# 06_-_FPGA_Aux.net
KiCad netlist of a schematic drawn in Altium Designer
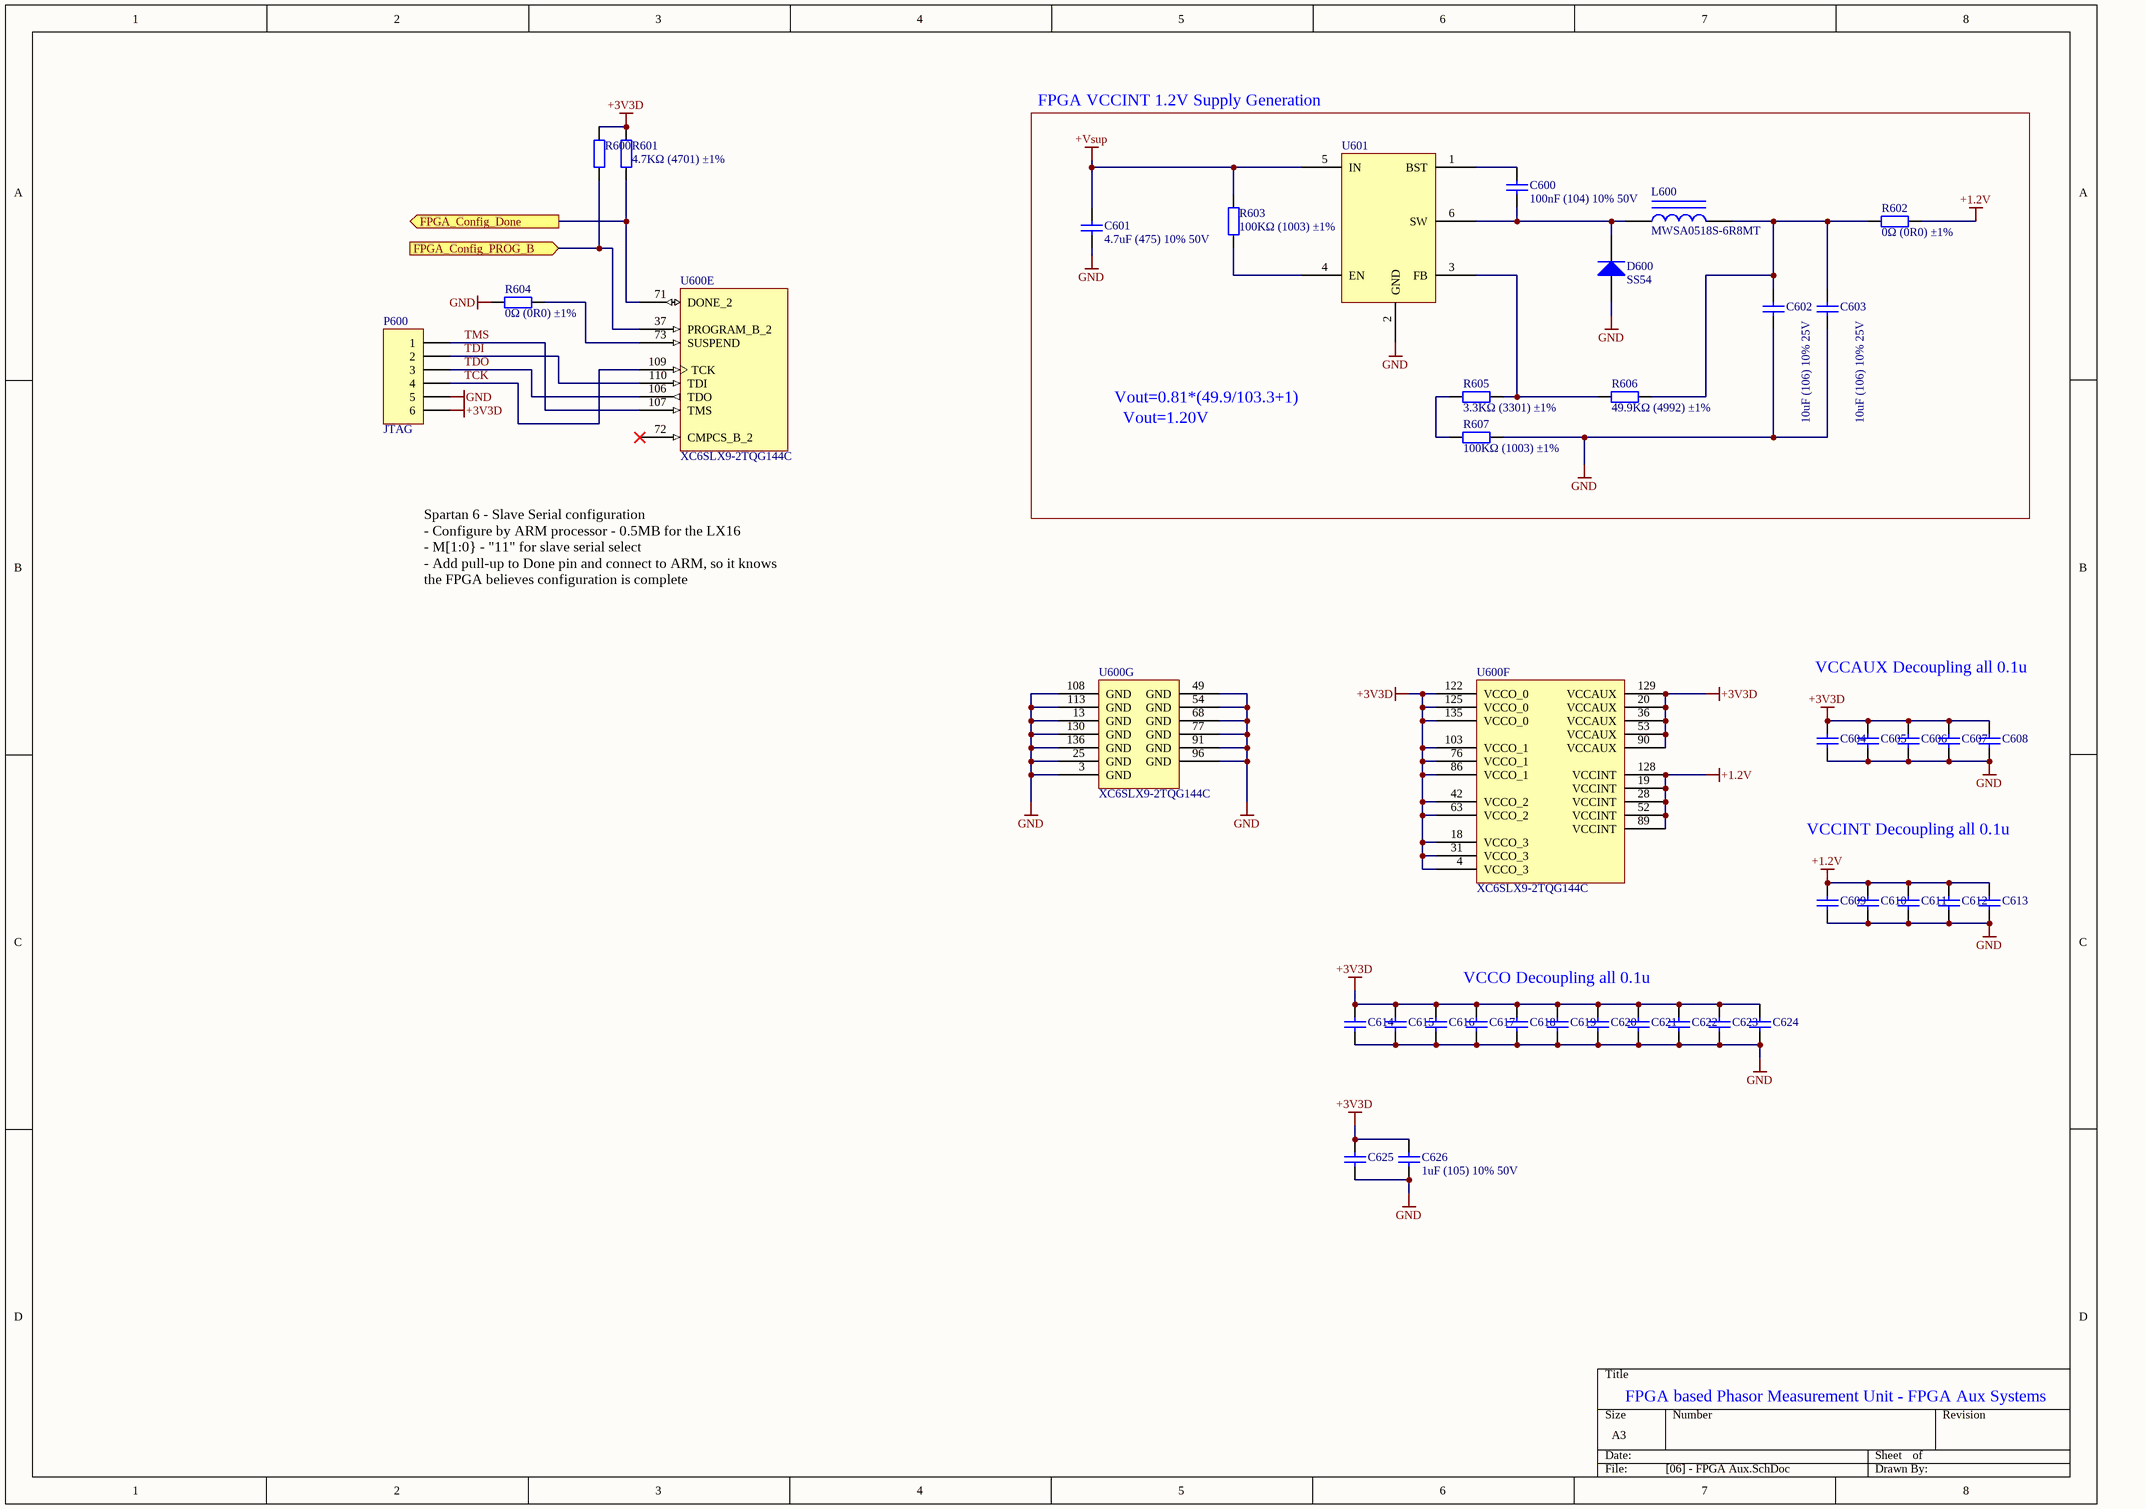
[diagram p0: [06] - FPGA Aux.SchDoc]

(export (version "E")
  (design (tool "Eeschema 10.0.6"))
  (components
    (comp (ref "C600")
      (value "100nF (104) 10% 50V")
      (footprint "0603_C")
      (description "贴片电容")
      (libsource (lib "Cap") (part "0603 100nF (104) 10% 50V"))
    )
    (comp (ref "C601")
      (value "4.7uF (475) 10% 50V")
      (footprint "1206_C")
      (description "贴片电容")
      (libsource (lib "Cap") (part "1206 4.7uF (475) 10% 50V"))
    )
    (comp (ref "C602")
      (value "10uF (106) 10% 25V")
      (footprint "0805_C")
      (description "贴片电容")
      (libsource (lib "Cap") (part "0805 10uF (106) 10% 25V"))
    )
    (comp (ref "C603")
      (value "10uF (106) 10% 25V")
      (footprint "0805_C")
      (description "贴片电容")
      (libsource (lib "Cap") (part "0805 10uF (106) 10% 25V"))
    )
    (comp (ref "C604")
      (value "100nF (104) 10% 16V")
      (footprint "0402_C")
      (description "贴片电容")
      (libsource (lib "Cap") (part "0402 100nF (104) 10% 16V"))
    )
    (comp (ref "C605")
      (value "100nF (104) 10% 16V")
      (footprint "0402_C")
      (description "贴片电容")
      (libsource (lib "Cap") (part "0402 100nF (104) 10% 16V"))
    )
    (comp (ref "C606")
      (value "100nF (104) 10% 16V")
      (footprint "0402_C")
      (description "贴片电容")
      (libsource (lib "Cap") (part "0402 100nF (104) 10% 16V"))
    )
    (comp (ref "C607")
      (value "100nF (104) 10% 16V")
      (footprint "0402_C")
      (description "贴片电容")
      (libsource (lib "Cap") (part "0402 100nF (104) 10% 16V"))
    )
    (comp (ref "C608")
      (value "100nF (104) 10% 16V")
      (footprint "0402_C")
      (description "贴片电容")
      (libsource (lib "Cap") (part "0402 100nF (104) 10% 16V"))
    )
    (comp (ref "C609")
      (value "100nF (104) 10% 16V")
      (footprint "0402_C")
      (description "贴片电容")
      (libsource (lib "Cap") (part "0402 100nF (104) 10% 16V"))
    )
    (comp (ref "C610")
      (value "100nF (104) 10% 16V")
      (footprint "0402_C")
      (description "贴片电容")
      (libsource (lib "Cap") (part "0402 100nF (104) 10% 16V"))
    )
    (comp (ref "C611")
      (value "100nF (104) 10% 16V")
      (footprint "0402_C")
      (description "贴片电容")
      (libsource (lib "Cap") (part "0402 100nF (104) 10% 16V"))
    )
    (comp (ref "C612")
      (value "100nF (104) 10% 16V")
      (footprint "0402_C")
      (description "贴片电容")
      (libsource (lib "Cap") (part "0402 100nF (104) 10% 16V"))
    )
    (comp (ref "C613")
      (value "100nF (104) 10% 16V")
      (footprint "0402_C")
      (description "贴片电容")
      (libsource (lib "Cap") (part "0402 100nF (104) 10% 16V"))
    )
    (comp (ref "C614")
      (value "100nF (104) 10% 16V")
      (footprint "0402_C")
      (description "贴片电容")
      (libsource (lib "Cap") (part "0402 100nF (104) 10% 16V"))
    )
    (comp (ref "C615")
      (value "100nF (104) 10% 16V")
      (footprint "0402_C")
      (description "贴片电容")
      (libsource (lib "Cap") (part "0402 100nF (104) 10% 16V"))
    )
    (comp (ref "C616")
      (value "100nF (104) 10% 16V")
      (footprint "0402_C")
      (description "贴片电容")
      (libsource (lib "Cap") (part "0402 100nF (104) 10% 16V"))
    )
    (comp (ref "C617")
      (value "100nF (104) 10% 16V")
      (footprint "0402_C")
      (description "贴片电容")
      (libsource (lib "Cap") (part "0402 100nF (104) 10% 16V"))
    )
    (comp (ref "C618")
      (value "100nF (104) 10% 16V")
      (footprint "0402_C")
      (description "贴片电容")
      (libsource (lib "Cap") (part "0402 100nF (104) 10% 16V"))
    )
    (comp (ref "C619")
      (value "100nF (104) 10% 16V")
      (footprint "0402_C")
      (description "贴片电容")
      (libsource (lib "Cap") (part "0402 100nF (104) 10% 16V"))
    )
    (comp (ref "C620")
      (value "100nF (104) 10% 16V")
      (footprint "0402_C")
      (description "贴片电容")
      (libsource (lib "Cap") (part "0402 100nF (104) 10% 16V"))
    )
    (comp (ref "C621")
      (value "100nF (104) 10% 16V")
      (footprint "0402_C")
      (description "贴片电容")
      (libsource (lib "Cap") (part "0402 100nF (104) 10% 16V"))
    )
    (comp (ref "C622")
      (value "100nF (104) 10% 16V")
      (footprint "0402_C")
      (description "贴片电容")
      (libsource (lib "Cap") (part "0402 100nF (104) 10% 16V"))
    )
    (comp (ref "C623")
      (value "100nF (104) 10% 16V")
      (footprint "0402_C")
      (description "贴片电容")
      (libsource (lib "Cap") (part "0402 100nF (104) 10% 16V"))
    )
    (comp (ref "C624")
      (value "100nF (104) 10% 16V")
      (footprint "0402_C")
      (description "贴片电容")
      (libsource (lib "Cap") (part "0402 100nF (104) 10% 16V"))
    )
    (comp (ref "C625")
      (value "1uF (105) 10% 50V")
      (footprint "0603_C")
      (description "贴片电容")
      (libsource (lib "Cap") (part "0603 1uF (105) 10% 50V"))
    )
    (comp (ref "C626")
      (value "1uF (105) 10% 50V")
      (footprint "0603_C")
      (description "贴片电容")
      (libsource (lib "Cap") (part "0603 1uF (105) 10% 50V"))
    )
    (comp (ref "D600")
      (value "SS54")
      (footprint "SMA(DO-214AC)_S1")
      (description "二极管")
      (libsource (lib "Diode") (part "SMA(DO-214AC) SS54"))
    )
    (comp (ref "L600")
      (value "MWSA0518S-6R8MT")
      (footprint "MWSA0518")
      (description "POWER INDUCTORS SMD,5.2X5.4X1.8MM ROHS")
      (libsource (lib "FPGA_PMU_lib") (part "MWSA0518S-6R8MT"))
    )
    (comp (ref "P600")
      (value "JTAG")
      (footprint "HDR1X6")
      (description "Header, 6-Pin")
      (fields (field (name "PUBLISHER") "Altium Limited"))
      (libsource (lib "Miscellaneous Connectors") (part "Header 6"))
    )
    (comp (ref "R600")
      (value "4.7KΩ (4701) ±1%")
      (footprint "0402_R")
      (description "贴片电阻")
      (libsource (lib "RES") (part "0402 4.7KΩ (4701) 1%"))
    )
    (comp (ref "R601")
      (value "4.7KΩ (4701) ±1%")
      (footprint "0402_R")
      (description "贴片电阻")
      (libsource (lib "RES") (part "0402 4.7KΩ (4701) 1%"))
    )
    (comp (ref "R602")
      (value "0Ω (0R0) ±1%")
      (footprint "0805_R")
      (description "贴片电阻")
      (libsource (lib "RES") (part "0805 0Ω (0R0) 1%"))
    )
    (comp (ref "R603")
      (value "100KΩ (1003) ±1%")
      (footprint "0402_R")
      (description "贴片电阻")
      (libsource (lib "") (part "0402 100KΩ (1003) 1%_1"))
    )
    (comp (ref "R604")
      (value "0Ω (0R0) ±1%")
      (footprint "0402_R")
      (description "贴片电阻")
      (libsource (lib "RES") (part "0402 0Ω (0R0) 1%"))
    )
    (comp (ref "R605")
      (value "3.3KΩ (3301) ±1%")
      (footprint "0402_R")
      (description "贴片电阻")
      (libsource (lib "RES") (part "0402 3.3KΩ (3301) 1%"))
    )
    (comp (ref "R606")
      (value "49.9KΩ (4992) ±1%")
      (footprint "0402_R")
      (description "贴片电阻")
      (libsource (lib "RES") (part "0402 49.9KΩ (4992) 1%"))
    )
    (comp (ref "R607")
      (value "100KΩ (1003) ±1%")
      (footprint "0402_R")
      (description "贴片电阻")
      (libsource (lib "RES") (part "0402 100KΩ (1003) 1%"))
    )
    (comp (ref "U600")
      (value "XC6SLX9-2TQG144C")
      (footprint "TQG144_N")
      (libsource (lib "Altium Content Vault") (part "FPGA-XSP6-XC6SLX9-SQ144"))
    )
    (comp (ref "U601")
      (value "STEP-DOWN CONVERTER")
      (footprint "*TSOT-23_S6")
      (description "1.2A, 24V, 1.4MHz STEP-DOWN CONVERTER IN A TSOT23-6")
      (libsource (lib "FPGA_PMU_lib") (part "MP2359"))
    )
  )
  (nets
    (net (code "1") (name "+1.2V") (class "Default")
      (node (ref "C609") (pin "2") (pinfunction "2_2") (pintype "passive"))
      (node (ref "C610") (pin "2") (pinfunction "2_2") (pintype "passive"))
      (node (ref "C611") (pin "2") (pinfunction "2_2") (pintype "passive"))
      (node (ref "C612") (pin "2") (pinfunction "2_2") (pintype "passive"))
      (node (ref "C613") (pin "2") (pinfunction "2_2") (pintype "passive"))
      (node (ref "R602") (pin "2") (pinfunction "2_2") (pintype "passive"))
      (node (ref "U600") (pin "128") (pinfunction "VCCINT_128") (pintype "power_in"))
      (node (ref "U600") (pin "19") (pinfunction "VCCINT_19") (pintype "power_in"))
      (node (ref "U600") (pin "28") (pinfunction "VCCINT_28") (pintype "power_in"))
      (node (ref "U600") (pin "52") (pinfunction "VCCINT_52") (pintype "power_in"))
      (node (ref "U600") (pin "89") (pinfunction "VCCINT_89") (pintype "power_in"))
    )
    (net (code "2") (name "+3V3D") (class "Default")
      (node (ref "C604") (pin "2") (pinfunction "2_2") (pintype "passive"))
      (node (ref "C605") (pin "2") (pinfunction "2_2") (pintype "passive"))
      (node (ref "C606") (pin "2") (pinfunction "2_2") (pintype "passive"))
      (node (ref "C607") (pin "2") (pinfunction "2_2") (pintype "passive"))
      (node (ref "C608") (pin "2") (pinfunction "2_2") (pintype "passive"))
      (node (ref "C614") (pin "2") (pinfunction "2_2") (pintype "passive"))
      (node (ref "C615") (pin "2") (pinfunction "2_2") (pintype "passive"))
      (node (ref "C616") (pin "2") (pinfunction "2_2") (pintype "passive"))
      (node (ref "C617") (pin "2") (pinfunction "2_2") (pintype "passive"))
      (node (ref "C618") (pin "2") (pinfunction "2_2") (pintype "passive"))
      (node (ref "C619") (pin "2") (pinfunction "2_2") (pintype "passive"))
      (node (ref "C620") (pin "2") (pinfunction "2_2") (pintype "passive"))
      (node (ref "C621") (pin "2") (pinfunction "2_2") (pintype "passive"))
      (node (ref "C622") (pin "2") (pinfunction "2_2") (pintype "passive"))
      (node (ref "C623") (pin "2") (pinfunction "2_2") (pintype "passive"))
      (node (ref "C624") (pin "2") (pinfunction "2_2") (pintype "passive"))
      (node (ref "C625") (pin "2") (pinfunction "2_2") (pintype "passive"))
      (node (ref "C626") (pin "2") (pinfunction "2_2") (pintype "passive"))
      (node (ref "P600") (pin "6") (pinfunction "6_6") (pintype "passive"))
      (node (ref "R600") (pin "2") (pinfunction "2_2") (pintype "passive"))
      (node (ref "R601") (pin "2") (pinfunction "2_2") (pintype "passive"))
      (node (ref "U600") (pin "103") (pinfunction "VCCO_1_103") (pintype "power_in"))
      (node (ref "U600") (pin "122") (pinfunction "VCCO_0_122") (pintype "power_in"))
      (node (ref "U600") (pin "125") (pinfunction "VCCO_0_125") (pintype "power_in"))
      (node (ref "U600") (pin "129") (pinfunction "VCCAUX_129") (pintype "power_in"))
      (node (ref "U600") (pin "135") (pinfunction "VCCO_0_135") (pintype "power_in"))
      (node (ref "U600") (pin "18") (pinfunction "VCCO_3_18") (pintype "power_in"))
      (node (ref "U600") (pin "20") (pinfunction "VCCAUX_20") (pintype "power_in"))
      (node (ref "U600") (pin "31") (pinfunction "VCCO_3_31") (pintype "power_in"))
      (node (ref "U600") (pin "36") (pinfunction "VCCAUX_36") (pintype "power_in"))
      (node (ref "U600") (pin "4") (pinfunction "VCCO_3_4") (pintype "power_in"))
      (node (ref "U600") (pin "42") (pinfunction "VCCO_2_42") (pintype "power_in"))
      (node (ref "U600") (pin "53") (pinfunction "VCCAUX_53") (pintype "power_in"))
      (node (ref "U600") (pin "63") (pinfunction "VCCO_2_63") (pintype "power_in"))
      (node (ref "U600") (pin "76") (pinfunction "VCCO_1_76") (pintype "power_in"))
      (node (ref "U600") (pin "86") (pinfunction "VCCO_1_86") (pintype "power_in"))
      (node (ref "U600") (pin "90") (pinfunction "VCCAUX_90") (pintype "power_in"))
    )
    (net (code "3") (name "+Vsup") (class "Default")
      (node (ref "C601") (pin "2") (pinfunction "2_2") (pintype "passive"))
      (node (ref "R603") (pin "2") (pinfunction "2_2") (pintype "passive"))
      (node (ref "U601") (pin "5") (pinfunction "IN_5") (pintype "passive"))
    )
    (net (code "4") (name "/FPGA_Config_Done") (class "Default")
      (node (ref "R601") (pin "1") (pinfunction "1_1") (pintype "passive"))
      (node (ref "U600") (pin "71") (pinfunction "DONE_2_71") (pintype "bidirectional"))
    )
    (net (code "5") (name "/FPGA_Config_PROG_B") (class "Default")
      (node (ref "R600") (pin "1") (pinfunction "1_1") (pintype "passive"))
      (node (ref "U600") (pin "37") (pinfunction "PROGRAM_B_2_37") (pintype "input"))
    )
    (net (code "6") (name "/TCK") (class "Default")
      (node (ref "P600") (pin "4") (pinfunction "4_4") (pintype "passive"))
      (node (ref "U600") (pin "109") (pinfunction "TCK_109") (pintype "input"))
    )
    (net (code "7") (name "/TDI") (class "Default")
      (node (ref "P600") (pin "2") (pinfunction "2_2") (pintype "passive"))
      (node (ref "U600") (pin "110") (pinfunction "TDI_110") (pintype "input"))
    )
    (net (code "8") (name "/TDO") (class "Default")
      (node (ref "P600") (pin "3") (pinfunction "3_3") (pintype "passive"))
      (node (ref "U600") (pin "106") (pinfunction "TDO_106") (pintype "output"))
    )
    (net (code "9") (name "/TMS") (class "Default")
      (node (ref "P600") (pin "1") (pinfunction "1_1") (pintype "passive"))
      (node (ref "U600") (pin "107") (pinfunction "TMS_107") (pintype "input"))
    )
    (net (code "10") (name "GND") (class "Default")
      (node (ref "C601") (pin "1") (pinfunction "1_1") (pintype "passive"))
      (node (ref "C602") (pin "1") (pinfunction "1_1") (pintype "passive"))
      (node (ref "C603") (pin "1") (pinfunction "1_1") (pintype "passive"))
      (node (ref "C604") (pin "1") (pinfunction "1_1") (pintype "passive"))
      (node (ref "C605") (pin "1") (pinfunction "1_1") (pintype "passive"))
      (node (ref "C606") (pin "1") (pinfunction "1_1") (pintype "passive"))
      (node (ref "C607") (pin "1") (pinfunction "1_1") (pintype "passive"))
      (node (ref "C608") (pin "1") (pinfunction "1_1") (pintype "passive"))
      (node (ref "C609") (pin "1") (pinfunction "1_1") (pintype "passive"))
      (node (ref "C610") (pin "1") (pinfunction "1_1") (pintype "passive"))
      (node (ref "C611") (pin "1") (pinfunction "1_1") (pintype "passive"))
      (node (ref "C612") (pin "1") (pinfunction "1_1") (pintype "passive"))
      (node (ref "C613") (pin "1") (pinfunction "1_1") (pintype "passive"))
      (node (ref "C614") (pin "1") (pinfunction "1_1") (pintype "passive"))
      (node (ref "C615") (pin "1") (pinfunction "1_1") (pintype "passive"))
      (node (ref "C616") (pin "1") (pinfunction "1_1") (pintype "passive"))
      (node (ref "C617") (pin "1") (pinfunction "1_1") (pintype "passive"))
      (node (ref "C618") (pin "1") (pinfunction "1_1") (pintype "passive"))
      (node (ref "C619") (pin "1") (pinfunction "1_1") (pintype "passive"))
      (node (ref "C620") (pin "1") (pinfunction "1_1") (pintype "passive"))
      (node (ref "C621") (pin "1") (pinfunction "1_1") (pintype "passive"))
      (node (ref "C622") (pin "1") (pinfunction "1_1") (pintype "passive"))
      (node (ref "C623") (pin "1") (pinfunction "1_1") (pintype "passive"))
      (node (ref "C624") (pin "1") (pinfunction "1_1") (pintype "passive"))
      (node (ref "C625") (pin "1") (pinfunction "1_1") (pintype "passive"))
      (node (ref "C626") (pin "1") (pinfunction "1_1") (pintype "passive"))
      (node (ref "D600") (pin "1") (pinfunction "A_1") (pintype "passive"))
      (node (ref "P600") (pin "5") (pinfunction "5_5") (pintype "passive"))
      (node (ref "R604") (pin "1") (pinfunction "1_1") (pintype "passive"))
      (node (ref "R607") (pin "1") (pinfunction "1_1") (pintype "passive"))
      (node (ref "U600") (pin "108") (pinfunction "GND_108") (pintype "power_in"))
      (node (ref "U600") (pin "113") (pinfunction "GND_113") (pintype "power_in"))
      (node (ref "U600") (pin "13") (pinfunction "GND_13") (pintype "power_in"))
      (node (ref "U600") (pin "130") (pinfunction "GND_130") (pintype "power_in"))
      (node (ref "U600") (pin "136") (pinfunction "GND_136") (pintype "power_in"))
      (node (ref "U600") (pin "25") (pinfunction "GND_25") (pintype "power_in"))
      (node (ref "U600") (pin "3") (pinfunction "GND_3") (pintype "power_in"))
      (node (ref "U600") (pin "49") (pinfunction "GND_49") (pintype "power_in"))
      (node (ref "U600") (pin "54") (pinfunction "GND_54") (pintype "power_in"))
      (node (ref "U600") (pin "68") (pinfunction "GND_68") (pintype "power_in"))
      (node (ref "U600") (pin "77") (pinfunction "GND_77") (pintype "power_in"))
      (node (ref "U600") (pin "91") (pinfunction "GND_91") (pintype "power_in"))
      (node (ref "U600") (pin "96") (pinfunction "GND_96") (pintype "power_in"))
      (node (ref "U601") (pin "2") (pinfunction "GND_2") (pintype "passive"))
    )
    (net (code "11") (name "Net-(C602-Pad2)") (class "Default")
      (node (ref "C602") (pin "2") (pinfunction "2_2") (pintype "passive"))
      (node (ref "C603") (pin "2") (pinfunction "2_2") (pintype "passive"))
      (node (ref "L600") (pin "2") (pinfunction "2_2") (pintype "power_in"))
      (node (ref "R602") (pin "1") (pinfunction "1_1") (pintype "passive"))
      (node (ref "R606") (pin "2") (pinfunction "2_2") (pintype "passive"))
    )
    (net (code "12") (name "Net-(D600-K)") (class "Default")
      (node (ref "C600") (pin "1") (pinfunction "1_1") (pintype "passive"))
      (node (ref "D600") (pin "2") (pinfunction "K_2") (pintype "passive"))
      (node (ref "L600") (pin "1") (pinfunction "1_1") (pintype "power_in"))
      (node (ref "U601") (pin "6") (pinfunction "SW_6") (pintype "passive"))
    )
    (net (code "13") (name "Net-(R605-Pad2)") (class "Default")
      (node (ref "R605") (pin "2") (pinfunction "2_2") (pintype "passive"))
      (node (ref "R607") (pin "2") (pinfunction "2_2") (pintype "passive"))
    )
    (net (code "14") (name "Net-(U600E-SUSPEND)") (class "Default")
      (node (ref "R604") (pin "2") (pinfunction "2_2") (pintype "passive"))
      (node (ref "U600") (pin "73") (pinfunction "SUSPEND_73") (pintype "input"))
    )
    (net (code "15") (name "Net-(U601-BST)") (class "Default")
      (node (ref "C600") (pin "2") (pinfunction "2_2") (pintype "passive"))
      (node (ref "U601") (pin "1") (pinfunction "BST_1") (pintype "passive"))
    )
    (net (code "16") (name "Net-(U601-EN)") (class "Default")
      (node (ref "R603") (pin "1") (pinfunction "1_1") (pintype "passive"))
      (node (ref "U601") (pin "4") (pinfunction "EN_4") (pintype "passive"))
    )
    (net (code "17") (name "Net-(U601-FB)") (class "Default")
      (node (ref "R605") (pin "1") (pinfunction "1_1") (pintype "passive"))
      (node (ref "R606") (pin "1") (pinfunction "1_1") (pintype "passive"))
      (node (ref "U601") (pin "3") (pinfunction "FB_3") (pintype "passive"))
    )
    (net (code "18") (name "unconnected-(U600E-CMPCS_B_2-Pad72)") (class "Default")
      (node (ref "U600") (pin "72") (pinfunction "CMPCS_B_2_72") (pintype "input+no_connect"))
    )
  )
)
